# lcd.net
KiCad netlist of a schematic drawn in EAGLE
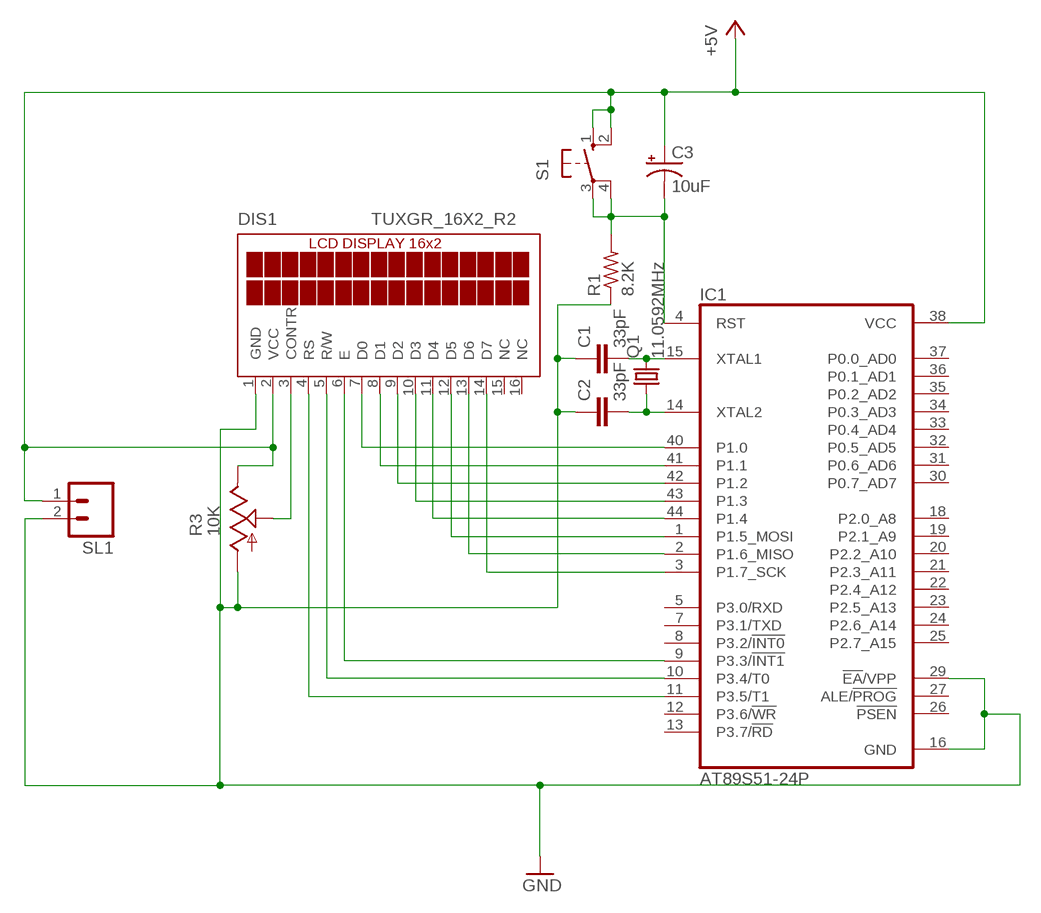
[diagram p0: schematic, sheet 1]

(export (version "E")
  (design (tool "Eeschema 10.0.6"))
  (components
    (comp (ref "C1")
      (value "33pF")
      (footprint "eagle-import:C1206K")
      (libsource (lib "eagle-import") (part "C-EUC1206K"))
    )
    (comp (ref "C2")
      (value "33pF")
      (footprint "eagle-import:C1206K")
      (libsource (lib "eagle-import") (part "C-EUC1206K"))
    )
    (comp (ref "C3")
      (value "10uF")
      (footprint "eagle-import:140CLH-1010")
      (libsource (lib "eagle-import") (part "CPOL-US140CLH-1010"))
    )
    (comp (ref "DIS1")
      (value "TUXGR_16X2_R2")
      (footprint "eagle-import:TUXGR_16X2_R2")
      (libsource (lib "eagle-import") (part "TUXGR_16X2_R2"))
    )
    (comp (ref "IC1")
      (value "AT89S51-24P")
      (footprint "eagle-import:TQFP44")
      (libsource (lib "eagle-import") (part "AT89S51P-24"))
    )
    (comp (ref "Q1")
      (value "11.0592MHz")
      (footprint "eagle-import:TC26V")
      (libsource (lib "eagle-import") (part "CRYSTALTC26V"))
    )
    (comp (ref "R1")
      (value "8.2K")
      (footprint "eagle-import:M1206")
      (libsource (lib "eagle-import") (part "R-US_M1206"))
    )
    (comp (ref "R3")
      (value "10K")
      (footprint "eagle-import:B25U")
      (libsource (lib "eagle-import") (part "TRIM_US-B25U"))
    )
    (comp (ref "S1")
      (value "10-XX")
      (footprint "eagle-import:B3F-10XX")
      (fields (field (name "MPN") "B3F-1000"))
      (libsource (lib "eagle-import") (part "10-XX"))
    )
    (comp (ref "SL1")
      (value "MA02")
      (footprint "eagle-import:02PA")
      (libsource (lib "eagle-import") (part "MA02"))
    )
  )
  (nets
    (net (code "1") (name "+5V") (class "Default")
      (node (ref "C3") (pin "+") (pinfunction "+_+") (pintype "passive"))
      (node (ref "DIS1") (pin "2") (pinfunction "VCC_2") (pintype "power_in"))
      (node (ref "IC1") (pin "38") (pinfunction "VCC_38") (pintype "power_in"))
      (node (ref "R3") (pin "E") (pinfunction "E_E") (pintype "passive"))
      (node (ref "S1") (pin "1") (pinfunction "S_1") (pintype "passive"))
      (node (ref "S1") (pin "2") (pinfunction "S1_2") (pintype "passive"))
      (node (ref "SL1") (pin "1") (pinfunction "1_1") (pintype "passive"))
    )
    (net (code "2") (name "GND") (class "Default")
      (node (ref "C1") (pin "1") (pinfunction "1_1") (pintype "passive"))
      (node (ref "C2") (pin "1") (pinfunction "1_1") (pintype "passive"))
      (node (ref "DIS1") (pin "1") (pinfunction "GND_1") (pintype "power_in"))
      (node (ref "IC1") (pin "16") (pinfunction "GND_16") (pintype "power_in"))
      (node (ref "IC1") (pin "29") (pinfunction "~{EA}/VPP_29") (pintype "input"))
      (node (ref "R1") (pin "1") (pinfunction "1_1") (pintype "passive"))
      (node (ref "R3") (pin "A") (pinfunction "A_A") (pintype "passive"))
      (node (ref "SL1") (pin "2") (pinfunction "2_2") (pintype "passive"))
    )
    (net (code "3") (name "Net-(DIS1-CONTR)") (class "Default")
      (node (ref "DIS1") (pin "3") (pinfunction "CONTR_3") (pintype "input"))
      (node (ref "R3") (pin "S") (pinfunction "S_S") (pintype "passive"))
    )
    (net (code "4") (name "Net-(DIS1-D0)") (class "Default")
      (node (ref "DIS1") (pin "7") (pinfunction "D0_7") (pintype "input"))
      (node (ref "IC1") (pin "40") (pinfunction "P1.0_40") (pintype "bidirectional"))
    )
    (net (code "5") (name "Net-(DIS1-D1)") (class "Default")
      (node (ref "DIS1") (pin "8") (pinfunction "D1_8") (pintype "input"))
      (node (ref "IC1") (pin "41") (pinfunction "P1.1_41") (pintype "bidirectional"))
    )
    (net (code "6") (name "Net-(DIS1-D2)") (class "Default")
      (node (ref "DIS1") (pin "9") (pinfunction "D2_9") (pintype "input"))
      (node (ref "IC1") (pin "42") (pinfunction "P1.2_42") (pintype "bidirectional"))
    )
    (net (code "7") (name "Net-(DIS1-D3)") (class "Default")
      (node (ref "DIS1") (pin "10") (pinfunction "D3_10") (pintype "input"))
      (node (ref "IC1") (pin "43") (pinfunction "P1.3_43") (pintype "bidirectional"))
    )
    (net (code "8") (name "Net-(DIS1-D4)") (class "Default")
      (node (ref "DIS1") (pin "11") (pinfunction "D4_11") (pintype "input"))
      (node (ref "IC1") (pin "44") (pinfunction "P1.4_44") (pintype "bidirectional"))
    )
    (net (code "9") (name "Net-(DIS1-D5)") (class "Default")
      (node (ref "DIS1") (pin "12") (pinfunction "D5_12") (pintype "input"))
      (node (ref "IC1") (pin "1") (pinfunction "P1.5_MOSI_1") (pintype "bidirectional"))
    )
    (net (code "10") (name "Net-(DIS1-D6)") (class "Default")
      (node (ref "DIS1") (pin "13") (pinfunction "D6_13") (pintype "input"))
      (node (ref "IC1") (pin "2") (pinfunction "P1.6_MISO_2") (pintype "bidirectional"))
    )
    (net (code "11") (name "Net-(DIS1-D7)") (class "Default")
      (node (ref "DIS1") (pin "14") (pinfunction "D7_14") (pintype "input"))
      (node (ref "IC1") (pin "3") (pinfunction "P1.7_SCK_3") (pintype "bidirectional"))
    )
    (net (code "12") (name "Net-(DIS1-E)") (class "Default")
      (node (ref "DIS1") (pin "6") (pinfunction "E_6") (pintype "input"))
      (node (ref "IC1") (pin "9") (pinfunction "P3.3/~{INT1}_9") (pintype "bidirectional"))
    )
    (net (code "13") (name "Net-(DIS1-RS)") (class "Default")
      (node (ref "DIS1") (pin "4") (pinfunction "RS_4") (pintype "input"))
      (node (ref "IC1") (pin "11") (pinfunction "P3.5/T1_11") (pintype "bidirectional"))
    )
    (net (code "14") (name "Net-(DIS1-R{slash}W)") (class "Default")
      (node (ref "DIS1") (pin "5") (pinfunction "R/W_5") (pintype "input"))
      (node (ref "IC1") (pin "10") (pinfunction "P3.4/T0_10") (pintype "bidirectional"))
    )
    (net (code "15") (name "Net-(IC1A-RST)") (class "Default")
      (node (ref "C3") (pin "-") (pinfunction "-_-") (pintype "passive"))
      (node (ref "IC1") (pin "4") (pinfunction "RST_4") (pintype "input"))
      (node (ref "R1") (pin "2") (pinfunction "2_2") (pintype "passive"))
      (node (ref "S1") (pin "3") (pinfunction "P_3") (pintype "passive"))
      (node (ref "S1") (pin "4") (pinfunction "P1_4") (pintype "passive"))
    )
    (net (code "16") (name "Net-(IC1A-XTAL1)") (class "Default")
      (node (ref "C1") (pin "2") (pinfunction "2_2") (pintype "passive"))
      (node (ref "IC1") (pin "15") (pinfunction "XTAL1_15") (pintype "input"))
      (node (ref "Q1") (pin "2") (pinfunction "2_2") (pintype "passive"))
    )
    (net (code "17") (name "Net-(IC1A-XTAL2)") (class "Default")
      (node (ref "C2") (pin "2") (pinfunction "2_2") (pintype "passive"))
      (node (ref "IC1") (pin "14") (pinfunction "XTAL2_14") (pintype "input"))
      (node (ref "Q1") (pin "1") (pinfunction "1_1") (pintype "passive"))
    )
    (net (code "18") (name "unconnected-(DIS1-NC-Pad15)") (class "Default")
      (node (ref "DIS1") (pin "15") (pinfunction "NC_15") (pintype "no_connect"))
    )
    (net (code "19") (name "unconnected-(DIS1-NC-Pad16)") (class "Default")
      (node (ref "DIS1") (pin "16") (pinfunction "NC_16") (pintype "no_connect"))
    )
    (net (code "20") (name "unconnected-(IC1A-ALE{slash}~{PROG}-Pad27)") (class "Default")
      (node (ref "IC1") (pin "27") (pinfunction "ALE/~{PROG}_27") (pintype "output"))
    )
    (net (code "21") (name "unconnected-(IC1A-P0.0_AD0-Pad37)") (class "Default")
      (node (ref "IC1") (pin "37") (pinfunction "P0.0_AD0_37") (pintype "bidirectional"))
    )
    (net (code "22") (name "unconnected-(IC1A-P0.1_AD1-Pad36)") (class "Default")
      (node (ref "IC1") (pin "36") (pinfunction "P0.1_AD1_36") (pintype "bidirectional"))
    )
    (net (code "23") (name "unconnected-(IC1A-P0.2_AD2-Pad35)") (class "Default")
      (node (ref "IC1") (pin "35") (pinfunction "P0.2_AD2_35") (pintype "bidirectional"))
    )
    (net (code "24") (name "unconnected-(IC1A-P0.3_AD3-Pad34)") (class "Default")
      (node (ref "IC1") (pin "34") (pinfunction "P0.3_AD3_34") (pintype "bidirectional"))
    )
    (net (code "25") (name "unconnected-(IC1A-P0.4_AD4-Pad33)") (class "Default")
      (node (ref "IC1") (pin "33") (pinfunction "P0.4_AD4_33") (pintype "bidirectional"))
    )
    (net (code "26") (name "unconnected-(IC1A-P0.5_AD5-Pad32)") (class "Default")
      (node (ref "IC1") (pin "32") (pinfunction "P0.5_AD5_32") (pintype "bidirectional"))
    )
    (net (code "27") (name "unconnected-(IC1A-P0.6_AD6-Pad31)") (class "Default")
      (node (ref "IC1") (pin "31") (pinfunction "P0.6_AD6_31") (pintype "bidirectional"))
    )
    (net (code "28") (name "unconnected-(IC1A-P0.7_AD7-Pad30)") (class "Default")
      (node (ref "IC1") (pin "30") (pinfunction "P0.7_AD7_30") (pintype "bidirectional"))
    )
    (net (code "29") (name "unconnected-(IC1A-P2.0_A8-Pad18)") (class "Default")
      (node (ref "IC1") (pin "18") (pinfunction "P2.0_A8_18") (pintype "bidirectional"))
    )
    (net (code "30") (name "unconnected-(IC1A-P2.1_A9-Pad19)") (class "Default")
      (node (ref "IC1") (pin "19") (pinfunction "P2.1_A9_19") (pintype "bidirectional"))
    )
    (net (code "31") (name "unconnected-(IC1A-P2.2_A10-Pad20)") (class "Default")
      (node (ref "IC1") (pin "20") (pinfunction "P2.2_A10_20") (pintype "bidirectional"))
    )
    (net (code "32") (name "unconnected-(IC1A-P2.3_A11-Pad21)") (class "Default")
      (node (ref "IC1") (pin "21") (pinfunction "P2.3_A11_21") (pintype "bidirectional"))
    )
    (net (code "33") (name "unconnected-(IC1A-P2.4_A12-Pad22)") (class "Default")
      (node (ref "IC1") (pin "22") (pinfunction "P2.4_A12_22") (pintype "bidirectional"))
    )
    (net (code "34") (name "unconnected-(IC1A-P2.5_A13-Pad23)") (class "Default")
      (node (ref "IC1") (pin "23") (pinfunction "P2.5_A13_23") (pintype "bidirectional"))
    )
    (net (code "35") (name "unconnected-(IC1A-P2.6_A14-Pad24)") (class "Default")
      (node (ref "IC1") (pin "24") (pinfunction "P2.6_A14_24") (pintype "bidirectional"))
    )
    (net (code "36") (name "unconnected-(IC1A-P2.7_A15-Pad25)") (class "Default")
      (node (ref "IC1") (pin "25") (pinfunction "P2.7_A15_25") (pintype "bidirectional"))
    )
    (net (code "37") (name "unconnected-(IC1A-P3.0{slash}RXD-Pad5)") (class "Default")
      (node (ref "IC1") (pin "5") (pinfunction "P3.0/RXD_5") (pintype "bidirectional"))
    )
    (net (code "38") (name "unconnected-(IC1A-P3.1{slash}TXD-Pad7)") (class "Default")
      (node (ref "IC1") (pin "7") (pinfunction "P3.1/TXD_7") (pintype "bidirectional"))
    )
    (net (code "39") (name "unconnected-(IC1A-P3.2{slash}~{INT0}-Pad8)") (class "Default")
      (node (ref "IC1") (pin "8") (pinfunction "P3.2/~{INT0}_8") (pintype "bidirectional"))
    )
    (net (code "40") (name "unconnected-(IC1A-P3.6{slash}~{WR}-Pad12)") (class "Default")
      (node (ref "IC1") (pin "12") (pinfunction "P3.6/~{WR}_12") (pintype "bidirectional"))
    )
    (net (code "41") (name "unconnected-(IC1A-P3.7{slash}~{RD}-Pad13)") (class "Default")
      (node (ref "IC1") (pin "13") (pinfunction "P3.7/~{RD}_13") (pintype "bidirectional"))
    )
    (net (code "42") (name "unconnected-(IC1A-~{PSEN}-Pad26)") (class "Default")
      (node (ref "IC1") (pin "26") (pinfunction "~{PSEN}_26") (pintype "output"))
    )
  )
)
